# 4A_adjustable.net
KiCad netlist of a schematic drawn in EAGLE
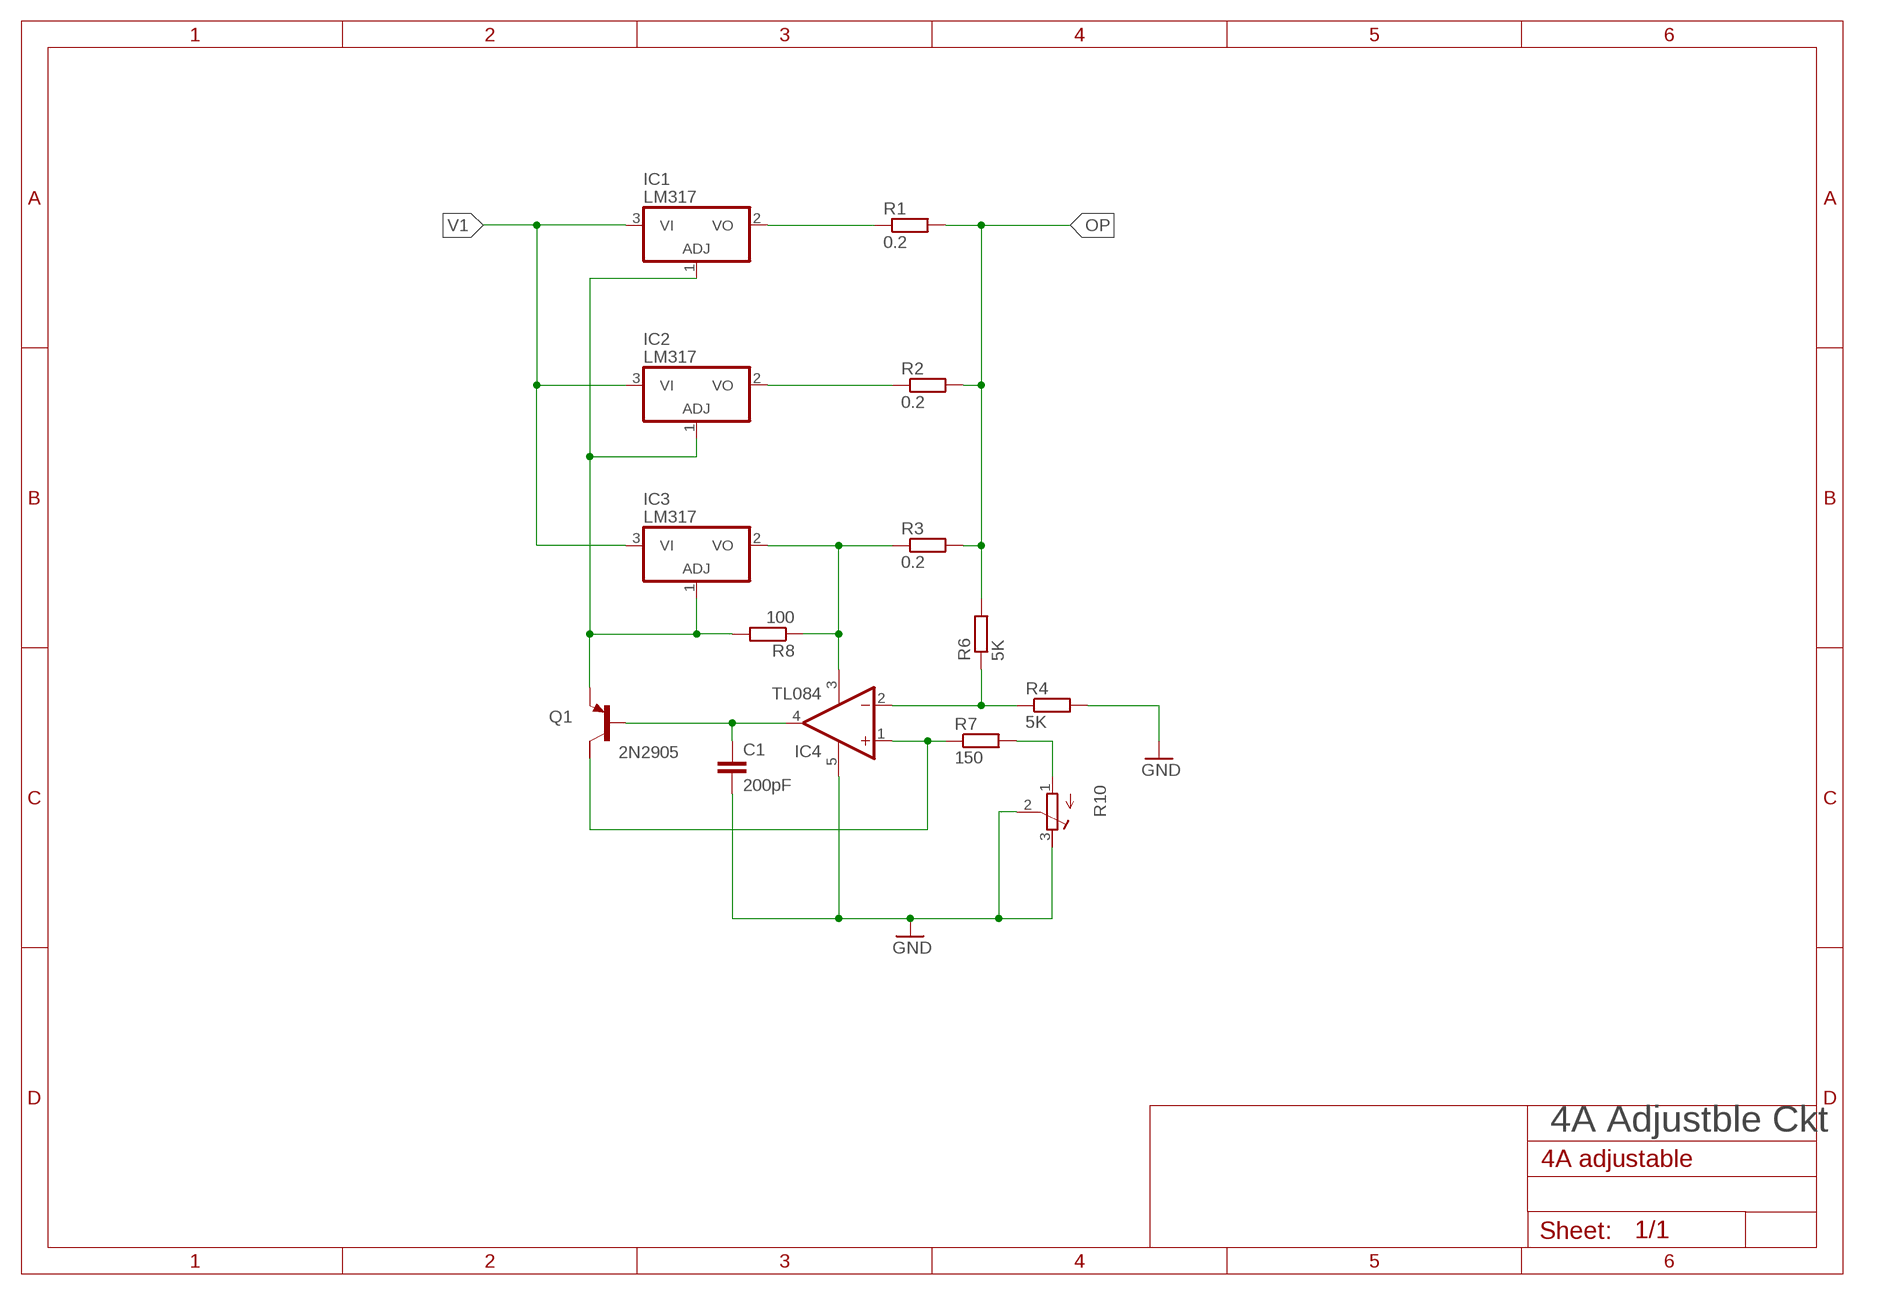
[diagram p0: schematic, sheet 1]

(export (version "E")
  (design (tool "Eeschema 10.0.6"))
  (components
    (comp (ref "C1")
      (value "200pF")
      (footprint "eagle-import:C025-025X050")
      (libsource (lib "eagle-import") (part "C-EU025-025X050"))
    )
    (comp (ref "IC1")
      (value "LM317")
      (footprint "eagle-import:TO92")
      (libsource (lib "eagle-import") (part "317LZLM"))
    )
    (comp (ref "IC2")
      (value "LM317")
      (footprint "eagle-import:TO92")
      (libsource (lib "eagle-import") (part "317LZLM"))
    )
    (comp (ref "IC3")
      (value "LM317")
      (footprint "eagle-import:TO92")
      (libsource (lib "eagle-import") (part "317LZLM"))
    )
    (comp (ref "IC4")
      (value "TL084")
      (footprint "eagle-import:CB360")
      (libsource (lib "eagle-import") (part "L165ST"))
    )
    (comp (ref "Q1")
      (value "2N2905")
      (footprint "eagle-import:SOT89")
      (libsource (lib "eagle-import") (part "PNP-TRANSISTIOR-2COLSOT89"))
    )
    (comp (ref "R1")
      (value "0.2")
      (footprint "eagle-import:0207_10")
      (libsource (lib "eagle-import") (part "R-EU_0207/10"))
    )
    (comp (ref "R2")
      (value "0.2")
      (footprint "eagle-import:0207_10")
      (libsource (lib "eagle-import") (part "R-EU_0207/10"))
    )
    (comp (ref "R3")
      (value "0.2")
      (footprint "eagle-import:0207_10")
      (libsource (lib "eagle-import") (part "R-EU_0207/10"))
    )
    (comp (ref "R4")
      (value "5K")
      (footprint "eagle-import:0207_10")
      (libsource (lib "eagle-import") (part "R-EU_0207/10"))
    )
    (comp (ref "R6")
      (value "5K")
      (footprint "eagle-import:0207_10")
      (libsource (lib "eagle-import") (part "R-EU_0207/10"))
    )
    (comp (ref "R7")
      (value "150")
      (footprint "eagle-import:0207_10")
      (libsource (lib "eagle-import") (part "R-EU_0207/10"))
    )
    (comp (ref "R8")
      (value "100")
      (footprint "eagle-import:0207_10")
      (libsource (lib "eagle-import") (part "R-EU_0207/10"))
    )
    (comp (ref "R10")
      (value "R-TRIMM3339P")
      (footprint "eagle-import:RTRIM3339P")
      (libsource (lib "eagle-import") (part "R-TRIMM3339P"))
    )
  )
  (nets
    (net (code "1") (name "GND") (class "Default")
      (node (ref "C1") (pin "2") (pinfunction "2_2") (pintype "passive"))
      (node (ref "IC4") (pin "5") (pinfunction "V+_5") (pintype "power_in"))
      (node (ref "R10") (pin "2") (pinfunction "S_2") (pintype "passive"))
      (node (ref "R10") (pin "3") (pinfunction "E_3") (pintype "passive"))
      (node (ref "R4") (pin "2") (pinfunction "2_2") (pintype "passive"))
    )
    (net (code "2") (name "Net-(IC1-ADJ)") (class "Default")
      (node (ref "IC1") (pin "1") (pinfunction "ADJ_1") (pintype "input"))
      (node (ref "IC2") (pin "1") (pinfunction "ADJ_1") (pintype "input"))
      (node (ref "IC3") (pin "1") (pinfunction "ADJ_1") (pintype "input"))
      (node (ref "Q1") (pin "3") (pinfunction "E_3") (pintype "passive"))
      (node (ref "R8") (pin "2") (pinfunction "2_2") (pintype "passive"))
    )
    (net (code "3") (name "Net-(IC1-VO)") (class "Default")
      (node (ref "IC1") (pin "2") (pinfunction "VO_2") (pintype "passive"))
      (node (ref "R1") (pin "1") (pinfunction "1_1") (pintype "passive"))
    )
    (net (code "4") (name "Net-(IC2-VO)") (class "Default")
      (node (ref "IC2") (pin "2") (pinfunction "VO_2") (pintype "passive"))
      (node (ref "R2") (pin "1") (pinfunction "1_1") (pintype "passive"))
    )
    (net (code "5") (name "Net-(IC3-VO)") (class "Default")
      (node (ref "IC3") (pin "2") (pinfunction "VO_2") (pintype "passive"))
      (node (ref "IC4") (pin "3") (pinfunction "GND_3") (pintype "power_in"))
      (node (ref "R3") (pin "1") (pinfunction "1_1") (pintype "passive"))
      (node (ref "R8") (pin "1") (pinfunction "1_1") (pintype "passive"))
    )
    (net (code "6") (name "Net-(IC4-+IN)") (class "Default")
      (node (ref "IC4") (pin "1") (pinfunction "+IN_1") (pintype "input"))
      (node (ref "Q1") (pin "2") (pinfunction "C_2") (pintype "passive"))
      (node (ref "R7") (pin "1") (pinfunction "1_1") (pintype "passive"))
    )
    (net (code "7") (name "Net-(IC4--IN)") (class "Default")
      (node (ref "IC4") (pin "2") (pinfunction "-IN_2") (pintype "input"))
      (node (ref "R4") (pin "1") (pinfunction "1_1") (pintype "passive"))
      (node (ref "R6") (pin "1") (pinfunction "1_1") (pintype "passive"))
    )
    (net (code "8") (name "Net-(IC4-OUT)") (class "Default")
      (node (ref "C1") (pin "1") (pinfunction "1_1") (pintype "passive"))
      (node (ref "IC4") (pin "4") (pinfunction "OUT_4") (pintype "output"))
      (node (ref "Q1") (pin "1") (pinfunction "B_1") (pintype "passive"))
    )
    (net (code "9") (name "Net-(R10-A)") (class "Default")
      (node (ref "R10") (pin "1") (pinfunction "A_1") (pintype "passive"))
      (node (ref "R7") (pin "2") (pinfunction "2_2") (pintype "passive"))
    )
    (net (code "10") (name "OP") (class "Default")
      (node (ref "R1") (pin "2") (pinfunction "2_2") (pintype "passive"))
      (node (ref "R2") (pin "2") (pinfunction "2_2") (pintype "passive"))
      (node (ref "R3") (pin "2") (pinfunction "2_2") (pintype "passive"))
      (node (ref "R6") (pin "2") (pinfunction "2_2") (pintype "passive"))
    )
    (net (code "11") (name "V1") (class "Default")
      (node (ref "IC1") (pin "3") (pinfunction "VI_3") (pintype "input"))
      (node (ref "IC2") (pin "3") (pinfunction "VI_3") (pintype "input"))
      (node (ref "IC3") (pin "3") (pinfunction "VI_3") (pintype "input"))
    )
    (net (code "12") (name "unconnected-(Q1-C{slash}-Pad2@1)") (class "Default")
      (node (ref "Q1") (pin "2@1") (pinfunction "C/_2@1") (pintype "passive"))
    )
  )
)
